# AlpLogo.net
KiCad netlist of a schematic drawn in Altium Designer
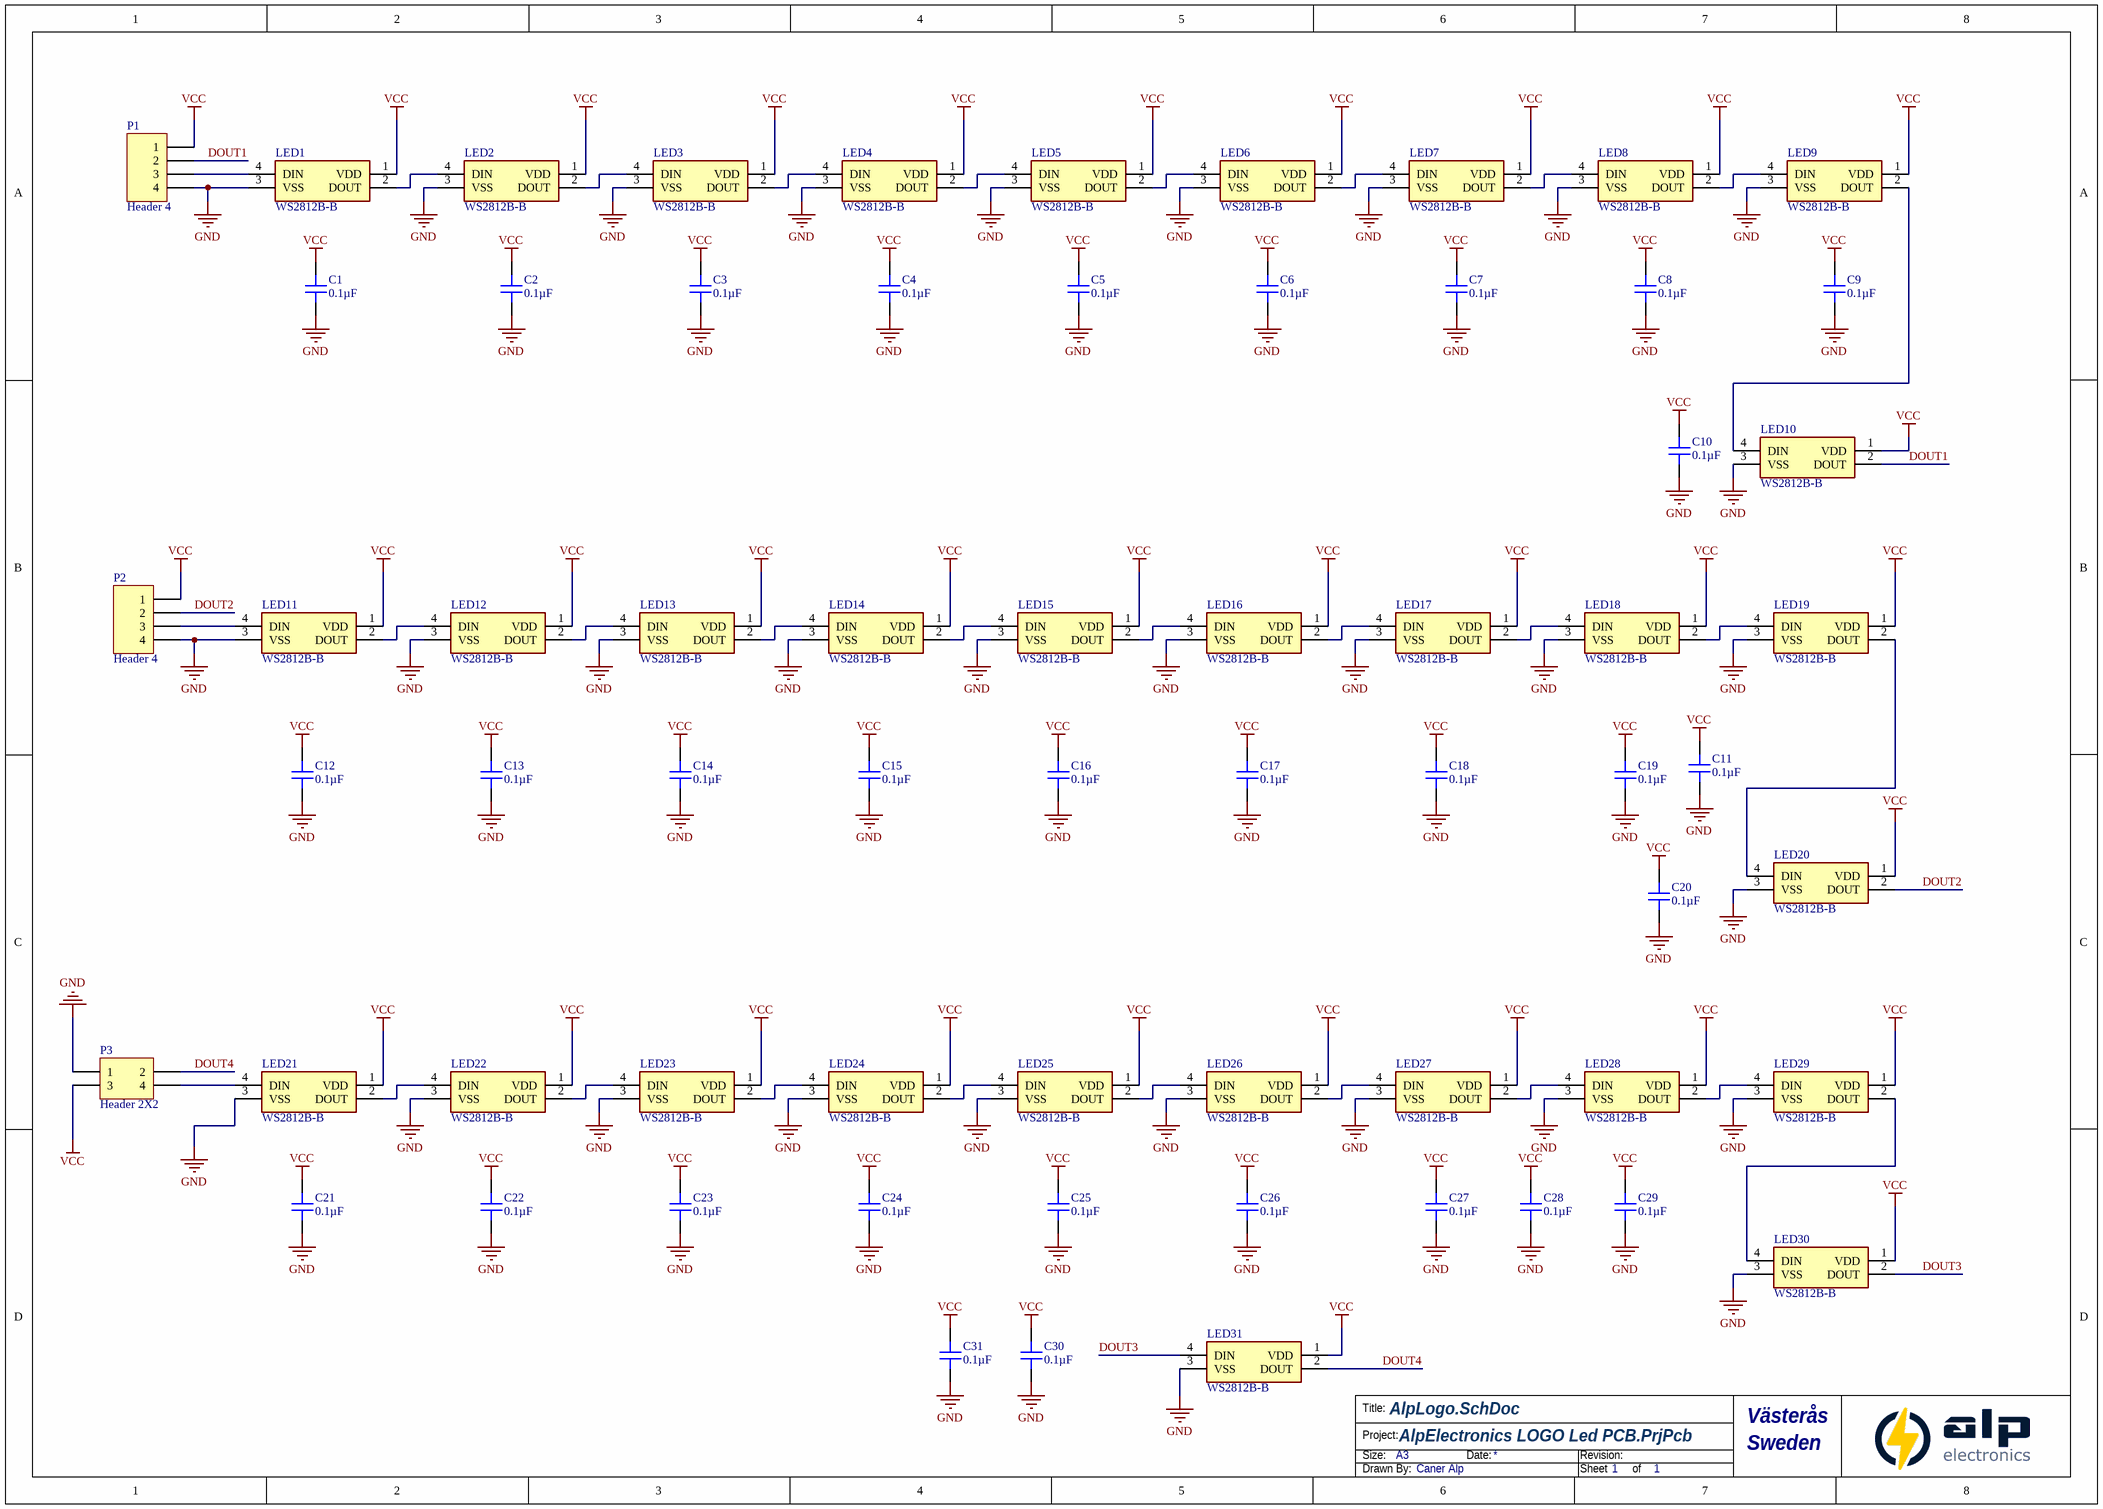
[diagram p0: AlpLogo.SchDoc]

(export (version "E")
  (design (tool "Eeschema 10.0.6"))
  (components
    (comp (ref "C1")
      (value "0.1µF")
      (footprint "CAP 0805_2012")
      (description "CAP CER 0.1UF 50V X7R 0805")
      (fields (field (name "PART NUMBER") "CC0805MRX7R9BB104") (field (name "MANUFACTURER") "Yageo"))
      (libsource (lib "Celestial Altium Library - altium_library") (part "Capacitor"))
    )
    (comp (ref "C2")
      (value "0.1µF")
      (footprint "CAP 0805_2012")
      (description "CAP CER 0.1UF 50V X7R 0805")
      (fields (field (name "PART NUMBER") "CC0805MRX7R9BB104") (field (name "MANUFACTURER") "Yageo"))
      (libsource (lib "Celestial Altium Library - altium_library") (part "Capacitor"))
    )
    (comp (ref "C3")
      (value "0.1µF")
      (footprint "CAP 0805_2012")
      (description "CAP CER 0.1UF 50V X7R 0805")
      (fields (field (name "PART NUMBER") "CC0805MRX7R9BB104") (field (name "MANUFACTURER") "Yageo"))
      (libsource (lib "Celestial Altium Library - altium_library") (part "Capacitor"))
    )
    (comp (ref "C4")
      (value "0.1µF")
      (footprint "CAP 0805_2012")
      (description "CAP CER 0.1UF 50V X7R 0805")
      (fields (field (name "PART NUMBER") "CC0805MRX7R9BB104") (field (name "MANUFACTURER") "Yageo"))
      (libsource (lib "Celestial Altium Library - altium_library") (part "Capacitor"))
    )
    (comp (ref "C5")
      (value "0.1µF")
      (footprint "CAP 0805_2012")
      (description "CAP CER 0.1UF 50V X7R 0805")
      (fields (field (name "PART NUMBER") "CC0805MRX7R9BB104") (field (name "MANUFACTURER") "Yageo"))
      (libsource (lib "Celestial Altium Library - altium_library") (part "Capacitor"))
    )
    (comp (ref "C6")
      (value "0.1µF")
      (footprint "CAP 0805_2012")
      (description "CAP CER 0.1UF 50V X7R 0805")
      (fields (field (name "PART NUMBER") "CC0805MRX7R9BB104") (field (name "MANUFACTURER") "Yageo"))
      (libsource (lib "Celestial Altium Library - altium_library") (part "Capacitor"))
    )
    (comp (ref "C7")
      (value "0.1µF")
      (footprint "CAP 0805_2012")
      (description "CAP CER 0.1UF 50V X7R 0805")
      (fields (field (name "PART NUMBER") "CC0805MRX7R9BB104") (field (name "MANUFACTURER") "Yageo"))
      (libsource (lib "Celestial Altium Library - altium_library") (part "Capacitor"))
    )
    (comp (ref "C8")
      (value "0.1µF")
      (footprint "CAP 0805_2012")
      (description "CAP CER 0.1UF 50V X7R 0805")
      (fields (field (name "PART NUMBER") "CC0805MRX7R9BB104") (field (name "MANUFACTURER") "Yageo"))
      (libsource (lib "Celestial Altium Library - altium_library") (part "Capacitor"))
    )
    (comp (ref "C9")
      (value "0.1µF")
      (footprint "CAP 0805_2012")
      (description "CAP CER 0.1UF 50V X7R 0805")
      (fields (field (name "PART NUMBER") "CC0805MRX7R9BB104") (field (name "MANUFACTURER") "Yageo"))
      (libsource (lib "Celestial Altium Library - altium_library") (part "Capacitor"))
    )
    (comp (ref "C10")
      (value "0.1µF")
      (footprint "CAP 0805_2012")
      (description "CAP CER 0.1UF 50V X7R 0805")
      (fields (field (name "PART NUMBER") "CC0805MRX7R9BB104") (field (name "MANUFACTURER") "Yageo"))
      (libsource (lib "Celestial Altium Library - altium_library") (part "Capacitor"))
    )
    (comp (ref "C11")
      (value "0.1µF")
      (footprint "CAP 0805_2012")
      (description "CAP CER 0.1UF 50V X7R 0805")
      (fields (field (name "PART NUMBER") "CC0805MRX7R9BB104") (field (name "MANUFACTURER") "Yageo"))
      (libsource (lib "Celestial Altium Library - altium_library") (part "Capacitor"))
    )
    (comp (ref "C12")
      (value "0.1µF")
      (footprint "CAP 0805_2012")
      (description "CAP CER 0.1UF 50V X7R 0805")
      (fields (field (name "PART NUMBER") "CC0805MRX7R9BB104") (field (name "MANUFACTURER") "Yageo"))
      (libsource (lib "Celestial Altium Library - altium_library") (part "Capacitor"))
    )
    (comp (ref "C13")
      (value "0.1µF")
      (footprint "CAP 0805_2012")
      (description "CAP CER 0.1UF 50V X7R 0805")
      (fields (field (name "PART NUMBER") "CC0805MRX7R9BB104") (field (name "MANUFACTURER") "Yageo"))
      (libsource (lib "Celestial Altium Library - altium_library") (part "Capacitor"))
    )
    (comp (ref "C14")
      (value "0.1µF")
      (footprint "CAP 0805_2012")
      (description "CAP CER 0.1UF 50V X7R 0805")
      (fields (field (name "PART NUMBER") "CC0805MRX7R9BB104") (field (name "MANUFACTURER") "Yageo"))
      (libsource (lib "Celestial Altium Library - altium_library") (part "Capacitor"))
    )
    (comp (ref "C15")
      (value "0.1µF")
      (footprint "CAP 0805_2012")
      (description "CAP CER 0.1UF 50V X7R 0805")
      (fields (field (name "PART NUMBER") "CC0805MRX7R9BB104") (field (name "MANUFACTURER") "Yageo"))
      (libsource (lib "Celestial Altium Library - altium_library") (part "Capacitor"))
    )
    (comp (ref "C16")
      (value "0.1µF")
      (footprint "CAP 0805_2012")
      (description "CAP CER 0.1UF 50V X7R 0805")
      (fields (field (name "PART NUMBER") "CC0805MRX7R9BB104") (field (name "MANUFACTURER") "Yageo"))
      (libsource (lib "Celestial Altium Library - altium_library") (part "Capacitor"))
    )
    (comp (ref "C17")
      (value "0.1µF")
      (footprint "CAP 0805_2012")
      (description "CAP CER 0.1UF 50V X7R 0805")
      (fields (field (name "PART NUMBER") "CC0805MRX7R9BB104") (field (name "MANUFACTURER") "Yageo"))
      (libsource (lib "Celestial Altium Library - altium_library") (part "Capacitor"))
    )
    (comp (ref "C18")
      (value "0.1µF")
      (footprint "CAP 0805_2012")
      (description "CAP CER 0.1UF 50V X7R 0805")
      (fields (field (name "PART NUMBER") "CC0805MRX7R9BB104") (field (name "MANUFACTURER") "Yageo"))
      (libsource (lib "Celestial Altium Library - altium_library") (part "Capacitor"))
    )
    (comp (ref "C19")
      (value "0.1µF")
      (footprint "CAP 0805_2012")
      (description "CAP CER 0.1UF 50V X7R 0805")
      (fields (field (name "PART NUMBER") "CC0805MRX7R9BB104") (field (name "MANUFACTURER") "Yageo"))
      (libsource (lib "Celestial Altium Library - altium_library") (part "Capacitor"))
    )
    (comp (ref "C20")
      (value "0.1µF")
      (footprint "CAP 0805_2012")
      (description "CAP CER 0.1UF 50V X7R 0805")
      (fields (field (name "PART NUMBER") "CC0805MRX7R9BB104") (field (name "MANUFACTURER") "Yageo"))
      (libsource (lib "Celestial Altium Library - altium_library") (part "Capacitor"))
    )
    (comp (ref "C21")
      (value "0.1µF")
      (footprint "CAP 0805_2012")
      (description "CAP CER 0.1UF 50V X7R 0805")
      (fields (field (name "PART NUMBER") "CC0805MRX7R9BB104") (field (name "MANUFACTURER") "Yageo"))
      (libsource (lib "Celestial Altium Library - altium_library") (part "Capacitor"))
    )
    (comp (ref "C22")
      (value "0.1µF")
      (footprint "CAP 0805_2012")
      (description "CAP CER 0.1UF 50V X7R 0805")
      (fields (field (name "PART NUMBER") "CC0805MRX7R9BB104") (field (name "MANUFACTURER") "Yageo"))
      (libsource (lib "Celestial Altium Library - altium_library") (part "Capacitor"))
    )
    (comp (ref "C23")
      (value "0.1µF")
      (footprint "CAP 0805_2012")
      (description "CAP CER 0.1UF 50V X7R 0805")
      (fields (field (name "PART NUMBER") "CC0805MRX7R9BB104") (field (name "MANUFACTURER") "Yageo"))
      (libsource (lib "Celestial Altium Library - altium_library") (part "Capacitor"))
    )
    (comp (ref "C24")
      (value "0.1µF")
      (footprint "CAP 0805_2012")
      (description "CAP CER 0.1UF 50V X7R 0805")
      (fields (field (name "PART NUMBER") "CC0805MRX7R9BB104") (field (name "MANUFACTURER") "Yageo"))
      (libsource (lib "Celestial Altium Library - altium_library") (part "Capacitor"))
    )
    (comp (ref "C25")
      (value "0.1µF")
      (footprint "CAP 0805_2012")
      (description "CAP CER 0.1UF 50V X7R 0805")
      (fields (field (name "PART NUMBER") "CC0805MRX7R9BB104") (field (name "MANUFACTURER") "Yageo"))
      (libsource (lib "Celestial Altium Library - altium_library") (part "Capacitor"))
    )
    (comp (ref "C26")
      (value "0.1µF")
      (footprint "CAP 0805_2012")
      (description "CAP CER 0.1UF 50V X7R 0805")
      (fields (field (name "PART NUMBER") "CC0805MRX7R9BB104") (field (name "MANUFACTURER") "Yageo"))
      (libsource (lib "Celestial Altium Library - altium_library") (part "Capacitor"))
    )
    (comp (ref "C27")
      (value "0.1µF")
      (footprint "CAP 0805_2012")
      (description "CAP CER 0.1UF 50V X7R 0805")
      (fields (field (name "PART NUMBER") "CC0805MRX7R9BB104") (field (name "MANUFACTURER") "Yageo"))
      (libsource (lib "Celestial Altium Library - altium_library") (part "Capacitor"))
    )
    (comp (ref "C28")
      (value "0.1µF")
      (footprint "CAP 0805_2012")
      (description "CAP CER 0.1UF 50V X7R 0805")
      (fields (field (name "PART NUMBER") "CC0805MRX7R9BB104") (field (name "MANUFACTURER") "Yageo"))
      (libsource (lib "Celestial Altium Library - altium_library") (part "Capacitor"))
    )
    (comp (ref "C29")
      (value "0.1µF")
      (footprint "CAP 0805_2012")
      (description "CAP CER 0.1UF 50V X7R 0805")
      (fields (field (name "PART NUMBER") "CC0805MRX7R9BB104") (field (name "MANUFACTURER") "Yageo"))
      (libsource (lib "Celestial Altium Library - altium_library") (part "Capacitor"))
    )
    (comp (ref "C30")
      (value "0.1µF")
      (footprint "CAP 0805_2012")
      (description "CAP CER 0.1UF 50V X7R 0805")
      (fields (field (name "PART NUMBER") "CC0805MRX7R9BB104") (field (name "MANUFACTURER") "Yageo"))
      (libsource (lib "Celestial Altium Library - altium_library") (part "Capacitor"))
    )
    (comp (ref "C31")
      (value "0.1µF")
      (footprint "CAP 0805_2012")
      (description "CAP CER 0.1UF 50V X7R 0805")
      (fields (field (name "PART NUMBER") "CC0805MRX7R9BB104") (field (name "MANUFACTURER") "Yageo"))
      (libsource (lib "Celestial Altium Library - altium_library") (part "Capacitor"))
    )
    (comp (ref "LED1")
      (value "WS2812B-B")
      (footprint "AlpLogo:WS2812BB")
      (description "LED")
      (libsource (lib "AlpLogo") (part "WS2812B-B"))
    )
    (comp (ref "LED2")
      (value "WS2812B-B")
      (footprint "AlpLogo:WS2812BB")
      (description "LED")
      (libsource (lib "AlpLogo") (part "WS2812B-B"))
    )
    (comp (ref "LED3")
      (value "WS2812B-B")
      (footprint "AlpLogo:WS2812BB")
      (description "LED")
      (libsource (lib "AlpLogo") (part "WS2812B-B"))
    )
    (comp (ref "LED4")
      (value "WS2812B-B")
      (footprint "AlpLogo:WS2812BB")
      (description "LED")
      (libsource (lib "AlpLogo") (part "WS2812B-B"))
    )
    (comp (ref "LED5")
      (value "WS2812B-B")
      (footprint "AlpLogo:WS2812BB")
      (description "LED")
      (libsource (lib "AlpLogo") (part "WS2812B-B"))
    )
    (comp (ref "LED6")
      (value "WS2812B-B")
      (footprint "AlpLogo:WS2812BB")
      (description "LED")
      (libsource (lib "AlpLogo") (part "WS2812B-B"))
    )
    (comp (ref "LED7")
      (value "WS2812B-B")
      (footprint "AlpLogo:WS2812BB")
      (description "LED")
      (libsource (lib "AlpLogo") (part "WS2812B-B"))
    )
    (comp (ref "LED8")
      (value "WS2812B-B")
      (footprint "AlpLogo:WS2812BB")
      (description "LED")
      (libsource (lib "AlpLogo") (part "WS2812B-B"))
    )
    (comp (ref "LED9")
      (value "WS2812B-B")
      (footprint "AlpLogo:WS2812BB")
      (description "LED")
      (libsource (lib "AlpLogo") (part "WS2812B-B"))
    )
    (comp (ref "LED10")
      (value "WS2812B-B")
      (footprint "AlpLogo:WS2812BB")
      (description "LED")
      (libsource (lib "AlpLogo") (part "WS2812B-B"))
    )
    (comp (ref "LED11")
      (value "WS2812B-B")
      (footprint "AlpLogo:WS2812BB")
      (description "LED")
      (libsource (lib "AlpLogo") (part "WS2812B-B"))
    )
    (comp (ref "LED12")
      (value "WS2812B-B")
      (footprint "AlpLogo:WS2812BB")
      (description "LED")
      (libsource (lib "AlpLogo") (part "WS2812B-B"))
    )
    (comp (ref "LED13")
      (value "WS2812B-B")
      (footprint "AlpLogo:WS2812BB")
      (description "LED")
      (libsource (lib "AlpLogo") (part "WS2812B-B"))
    )
    (comp (ref "LED14")
      (value "WS2812B-B")
      (footprint "AlpLogo:WS2812BB")
      (description "LED")
      (libsource (lib "AlpLogo") (part "WS2812B-B"))
    )
    (comp (ref "LED15")
      (value "WS2812B-B")
      (footprint "AlpLogo:WS2812BB")
      (description "LED")
      (libsource (lib "AlpLogo") (part "WS2812B-B"))
    )
    (comp (ref "LED16")
      (value "WS2812B-B")
      (footprint "AlpLogo:WS2812BB")
      (description "LED")
      (libsource (lib "AlpLogo") (part "WS2812B-B"))
    )
    (comp (ref "LED17")
      (value "WS2812B-B")
      (footprint "AlpLogo:WS2812BB")
      (description "LED")
      (libsource (lib "AlpLogo") (part "WS2812B-B"))
    )
    (comp (ref "LED18")
      (value "WS2812B-B")
      (footprint "AlpLogo:WS2812BB")
      (description "LED")
      (libsource (lib "AlpLogo") (part "WS2812B-B"))
    )
    (comp (ref "LED19")
      (value "WS2812B-B")
      (footprint "AlpLogo:WS2812BB")
      (description "LED")
      (libsource (lib "AlpLogo") (part "WS2812B-B"))
    )
    (comp (ref "LED20")
      (value "WS2812B-B")
      (footprint "AlpLogo:WS2812BB")
      (description "LED")
      (libsource (lib "AlpLogo") (part "WS2812B-B"))
    )
    (comp (ref "LED21")
      (value "WS2812B-B")
      (footprint "AlpLogo:WS2812BB")
      (description "LED")
      (libsource (lib "AlpLogo") (part "WS2812B-B"))
    )
    (comp (ref "LED22")
      (value "WS2812B-B")
      (footprint "AlpLogo:WS2812BB")
      (description "LED")
      (libsource (lib "AlpLogo") (part "WS2812B-B"))
    )
    (comp (ref "LED23")
      (value "WS2812B-B")
      (footprint "AlpLogo:WS2812BB")
      (description "LED")
      (libsource (lib "AlpLogo") (part "WS2812B-B"))
    )
    (comp (ref "LED24")
      (value "WS2812B-B")
      (footprint "AlpLogo:WS2812BB")
      (description "LED")
      (libsource (lib "AlpLogo") (part "WS2812B-B"))
    )
    (comp (ref "LED25")
      (value "WS2812B-B")
      (footprint "AlpLogo:WS2812BB")
      (description "LED")
      (libsource (lib "AlpLogo") (part "WS2812B-B"))
    )
    (comp (ref "LED26")
      (value "WS2812B-B")
      (footprint "AlpLogo:WS2812BB")
      (description "LED")
      (libsource (lib "AlpLogo") (part "WS2812B-B"))
    )
    (comp (ref "LED27")
      (value "WS2812B-B")
      (footprint "AlpLogo:WS2812BB")
      (description "LED")
      (libsource (lib "AlpLogo") (part "WS2812B-B"))
    )
    (comp (ref "LED28")
      (value "WS2812B-B")
      (footprint "AlpLogo:WS2812BB")
      (description "LED")
      (libsource (lib "AlpLogo") (part "WS2812B-B"))
    )
    (comp (ref "LED29")
      (value "WS2812B-B")
      (footprint "AlpLogo:WS2812BB")
      (description "LED")
      (libsource (lib "AlpLogo") (part "WS2812B-B"))
    )
    (comp (ref "LED30")
      (value "WS2812B-B")
      (footprint "AlpLogo:WS2812BB")
      (description "LED")
      (libsource (lib "AlpLogo") (part "WS2812B-B"))
    )
    (comp (ref "LED31")
      (value "WS2812B-B")
      (footprint "AlpLogo:WS2812BB")
      (description "LED")
      (libsource (lib "AlpLogo") (part "WS2812B-B"))
    )
    (comp (ref "P1")
      (value "Header 4")
      (footprint "HDR1X4")
      (description "Header, 4-Pin")
      (fields (field (name "PUBLISHER") "Altium Limited"))
      (libsource (lib "Miscellaneous Connectors") (part "Header 4"))
    )
    (comp (ref "P2")
      (value "Header 4")
      (footprint "HDR1X4")
      (description "Header, 4-Pin")
      (fields (field (name "PUBLISHER") "Altium Limited"))
      (libsource (lib "Miscellaneous Connectors") (part "Header 4"))
    )
    (comp (ref "P3")
      (value "Header 2X2")
      (footprint "HDR2X2")
      (description "Header, 2-Pin, Dual row")
      (fields (field (name "PUBLISHER") "Altium Limited"))
      (libsource (lib "Miscellaneous Connectors") (part "Header 2X2"))
    )
  )
  (nets
    (net (code "1") (name "/DOUT1") (class "Default")
      (node (ref "LED10") (pin "2") (pinfunction "DOUT_2") (pintype "passive"))
      (node (ref "P1") (pin "2") (pinfunction "2_2") (pintype "passive"))
    )
    (net (code "2") (name "/DOUT2") (class "Default")
      (node (ref "LED20") (pin "2") (pinfunction "DOUT_2") (pintype "passive"))
      (node (ref "P2") (pin "2") (pinfunction "2_2") (pintype "passive"))
    )
    (net (code "3") (name "/DOUT3") (class "Default")
      (node (ref "LED30") (pin "2") (pinfunction "DOUT_2") (pintype "passive"))
      (node (ref "LED31") (pin "4") (pinfunction "DIN_4") (pintype "passive"))
    )
    (net (code "4") (name "/DOUT4") (class "Default")
      (node (ref "LED31") (pin "2") (pinfunction "DOUT_2") (pintype "passive"))
      (node (ref "P3") (pin "2") (pinfunction "2_2") (pintype "passive"))
    )
    (net (code "5") (name "GND") (class "Default")
      (node (ref "C1") (pin "1") (pinfunction "1_1") (pintype "passive"))
      (node (ref "C10") (pin "1") (pinfunction "1_1") (pintype "passive"))
      (node (ref "C11") (pin "1") (pinfunction "1_1") (pintype "passive"))
      (node (ref "C12") (pin "1") (pinfunction "1_1") (pintype "passive"))
      (node (ref "C13") (pin "1") (pinfunction "1_1") (pintype "passive"))
      (node (ref "C14") (pin "1") (pinfunction "1_1") (pintype "passive"))
      (node (ref "C15") (pin "1") (pinfunction "1_1") (pintype "passive"))
      (node (ref "C16") (pin "1") (pinfunction "1_1") (pintype "passive"))
      (node (ref "C17") (pin "1") (pinfunction "1_1") (pintype "passive"))
      (node (ref "C18") (pin "1") (pinfunction "1_1") (pintype "passive"))
      (node (ref "C19") (pin "1") (pinfunction "1_1") (pintype "passive"))
      (node (ref "C2") (pin "1") (pinfunction "1_1") (pintype "passive"))
      (node (ref "C20") (pin "1") (pinfunction "1_1") (pintype "passive"))
      (node (ref "C21") (pin "1") (pinfunction "1_1") (pintype "passive"))
      (node (ref "C22") (pin "1") (pinfunction "1_1") (pintype "passive"))
      (node (ref "C23") (pin "1") (pinfunction "1_1") (pintype "passive"))
      (node (ref "C24") (pin "1") (pinfunction "1_1") (pintype "passive"))
      (node (ref "C25") (pin "1") (pinfunction "1_1") (pintype "passive"))
      (node (ref "C26") (pin "1") (pinfunction "1_1") (pintype "passive"))
      (node (ref "C27") (pin "1") (pinfunction "1_1") (pintype "passive"))
      (node (ref "C28") (pin "1") (pinfunction "1_1") (pintype "passive"))
      (node (ref "C29") (pin "1") (pinfunction "1_1") (pintype "passive"))
      (node (ref "C3") (pin "1") (pinfunction "1_1") (pintype "passive"))
      (node (ref "C30") (pin "1") (pinfunction "1_1") (pintype "passive"))
      (node (ref "C31") (pin "1") (pinfunction "1_1") (pintype "passive"))
      (node (ref "C4") (pin "1") (pinfunction "1_1") (pintype "passive"))
      (node (ref "C5") (pin "1") (pinfunction "1_1") (pintype "passive"))
      (node (ref "C6") (pin "1") (pinfunction "1_1") (pintype "passive"))
      (node (ref "C7") (pin "1") (pinfunction "1_1") (pintype "passive"))
      (node (ref "C8") (pin "1") (pinfunction "1_1") (pintype "passive"))
      (node (ref "C9") (pin "1") (pinfunction "1_1") (pintype "passive"))
      (node (ref "LED1") (pin "3") (pinfunction "VSS_3") (pintype "passive"))
      (node (ref "LED10") (pin "3") (pinfunction "VSS_3") (pintype "passive"))
      (node (ref "LED11") (pin "3") (pinfunction "VSS_3") (pintype "passive"))
      (node (ref "LED12") (pin "3") (pinfunction "VSS_3") (pintype "passive"))
      (node (ref "LED13") (pin "3") (pinfunction "VSS_3") (pintype "passive"))
      (node (ref "LED14") (pin "3") (pinfunction "VSS_3") (pintype "passive"))
      (node (ref "LED15") (pin "3") (pinfunction "VSS_3") (pintype "passive"))
      (node (ref "LED16") (pin "3") (pinfunction "VSS_3") (pintype "passive"))
      (node (ref "LED17") (pin "3") (pinfunction "VSS_3") (pintype "passive"))
      (node (ref "LED18") (pin "3") (pinfunction "VSS_3") (pintype "passive"))
      (node (ref "LED19") (pin "3") (pinfunction "VSS_3") (pintype "passive"))
      (node (ref "LED2") (pin "3") (pinfunction "VSS_3") (pintype "passive"))
      (node (ref "LED20") (pin "3") (pinfunction "VSS_3") (pintype "passive"))
      (node (ref "LED21") (pin "3") (pinfunction "VSS_3") (pintype "passive"))
      (node (ref "LED22") (pin "3") (pinfunction "VSS_3") (pintype "passive"))
      (node (ref "LED23") (pin "3") (pinfunction "VSS_3") (pintype "passive"))
      (node (ref "LED24") (pin "3") (pinfunction "VSS_3") (pintype "passive"))
      (node (ref "LED25") (pin "3") (pinfunction "VSS_3") (pintype "passive"))
      (node (ref "LED26") (pin "3") (pinfunction "VSS_3") (pintype "passive"))
      (node (ref "LED27") (pin "3") (pinfunction "VSS_3") (pintype "passive"))
      (node (ref "LED28") (pin "3") (pinfunction "VSS_3") (pintype "passive"))
      (node (ref "LED29") (pin "3") (pinfunction "VSS_3") (pintype "passive"))
      (node (ref "LED3") (pin "3") (pinfunction "VSS_3") (pintype "passive"))
      (node (ref "LED30") (pin "3") (pinfunction "VSS_3") (pintype "passive"))
      (node (ref "LED31") (pin "3") (pinfunction "VSS_3") (pintype "passive"))
      (node (ref "LED4") (pin "3") (pinfunction "VSS_3") (pintype "passive"))
      (node (ref "LED5") (pin "3") (pinfunction "VSS_3") (pintype "passive"))
      (node (ref "LED6") (pin "3") (pinfunction "VSS_3") (pintype "passive"))
      (node (ref "LED7") (pin "3") (pinfunction "VSS_3") (pintype "passive"))
      (node (ref "LED8") (pin "3") (pinfunction "VSS_3") (pintype "passive"))
      (node (ref "LED9") (pin "3") (pinfunction "VSS_3") (pintype "passive"))
      (node (ref "P1") (pin "4") (pinfunction "4_4") (pintype "passive"))
      (node (ref "P2") (pin "4") (pinfunction "4_4") (pintype "passive"))
      (node (ref "P3") (pin "1") (pinfunction "1_1") (pintype "passive"))
    )
    (net (code "6") (name "Net-(LED1-DIN)") (class "Default")
      (node (ref "LED1") (pin "4") (pinfunction "DIN_4") (pintype "passive"))
      (node (ref "P1") (pin "3") (pinfunction "3_3") (pintype "passive"))
    )
    (net (code "7") (name "Net-(LED1-DOUT)") (class "Default")
      (node (ref "LED1") (pin "2") (pinfunction "DOUT_2") (pintype "passive"))
      (node (ref "LED2") (pin "4") (pinfunction "DIN_4") (pintype "passive"))
    )
    (net (code "8") (name "Net-(LED2-DOUT)") (class "Default")
      (node (ref "LED2") (pin "2") (pinfunction "DOUT_2") (pintype "passive"))
      (node (ref "LED3") (pin "4") (pinfunction "DIN_4") (pintype "passive"))
    )
    (net (code "9") (name "Net-(LED3-DOUT)") (class "Default")
      (node (ref "LED3") (pin "2") (pinfunction "DOUT_2") (pintype "passive"))
      (node (ref "LED4") (pin "4") (pinfunction "DIN_4") (pintype "passive"))
    )
    (net (code "10") (name "Net-(LED4-DOUT)") (class "Default")
      (node (ref "LED4") (pin "2") (pinfunction "DOUT_2") (pintype "passive"))
      (node (ref "LED5") (pin "4") (pinfunction "DIN_4") (pintype "passive"))
    )
    (net (code "11") (name "Net-(LED5-DOUT)") (class "Default")
      (node (ref "LED5") (pin "2") (pinfunction "DOUT_2") (pintype "passive"))
      (node (ref "LED6") (pin "4") (pinfunction "DIN_4") (pintype "passive"))
    )
    (net (code "12") (name "Net-(LED6-DOUT)") (class "Default")
      (node (ref "LED6") (pin "2") (pinfunction "DOUT_2") (pintype "passive"))
      (node (ref "LED7") (pin "4") (pinfunction "DIN_4") (pintype "passive"))
    )
    (net (code "13") (name "Net-(LED7-DOUT)") (class "Default")
      (node (ref "LED7") (pin "2") (pinfunction "DOUT_2") (pintype "passive"))
      (node (ref "LED8") (pin "4") (pinfunction "DIN_4") (pintype "passive"))
    )
    (net (code "14") (name "Net-(LED8-DOUT)") (class "Default")
      (node (ref "LED8") (pin "2") (pinfunction "DOUT_2") (pintype "passive"))
      (node (ref "LED9") (pin "4") (pinfunction "DIN_4") (pintype "passive"))
    )
    (net (code "15") (name "Net-(LED10-DIN)") (class "Default")
      (node (ref "LED10") (pin "4") (pinfunction "DIN_4") (pintype "passive"))
      (node (ref "LED9") (pin "2") (pinfunction "DOUT_2") (pintype "passive"))
    )
    (net (code "16") (name "Net-(LED11-DIN)") (class "Default")
      (node (ref "LED11") (pin "4") (pinfunction "DIN_4") (pintype "passive"))
      (node (ref "P2") (pin "3") (pinfunction "3_3") (pintype "passive"))
    )
    (net (code "17") (name "Net-(LED11-DOUT)") (class "Default")
      (node (ref "LED11") (pin "2") (pinfunction "DOUT_2") (pintype "passive"))
      (node (ref "LED12") (pin "4") (pinfunction "DIN_4") (pintype "passive"))
    )
    (net (code "18") (name "Net-(LED12-DOUT)") (class "Default")
      (node (ref "LED12") (pin "2") (pinfunction "DOUT_2") (pintype "passive"))
      (node (ref "LED13") (pin "4") (pinfunction "DIN_4") (pintype "passive"))
    )
    (net (code "19") (name "Net-(LED13-DOUT)") (class "Default")
      (node (ref "LED13") (pin "2") (pinfunction "DOUT_2") (pintype "passive"))
      (node (ref "LED14") (pin "4") (pinfunction "DIN_4") (pintype "passive"))
    )
    (net (code "20") (name "Net-(LED14-DOUT)") (class "Default")
      (node (ref "LED14") (pin "2") (pinfunction "DOUT_2") (pintype "passive"))
      (node (ref "LED15") (pin "4") (pinfunction "DIN_4") (pintype "passive"))
    )
    (net (code "21") (name "Net-(LED15-DOUT)") (class "Default")
      (node (ref "LED15") (pin "2") (pinfunction "DOUT_2") (pintype "passive"))
      (node (ref "LED16") (pin "4") (pinfunction "DIN_4") (pintype "passive"))
    )
    (net (code "22") (name "Net-(LED16-DOUT)") (class "Default")
      (node (ref "LED16") (pin "2") (pinfunction "DOUT_2") (pintype "passive"))
      (node (ref "LED17") (pin "4") (pinfunction "DIN_4") (pintype "passive"))
    )
    (net (code "23") (name "Net-(LED17-DOUT)") (class "Default")
      (node (ref "LED17") (pin "2") (pinfunction "DOUT_2") (pintype "passive"))
      (node (ref "LED18") (pin "4") (pinfunction "DIN_4") (pintype "passive"))
    )
    (net (code "24") (name "Net-(LED18-DOUT)") (class "Default")
      (node (ref "LED18") (pin "2") (pinfunction "DOUT_2") (pintype "passive"))
      (node (ref "LED19") (pin "4") (pinfunction "DIN_4") (pintype "passive"))
    )
    (net (code "25") (name "Net-(LED19-DOUT)") (class "Default")
      (node (ref "LED19") (pin "2") (pinfunction "DOUT_2") (pintype "passive"))
      (node (ref "LED20") (pin "4") (pinfunction "DIN_4") (pintype "passive"))
    )
    (net (code "26") (name "Net-(LED21-DIN)") (class "Default")
      (node (ref "LED21") (pin "4") (pinfunction "DIN_4") (pintype "passive"))
      (node (ref "P3") (pin "4") (pinfunction "4_4") (pintype "passive"))
    )
    (net (code "27") (name "Net-(LED21-DOUT)") (class "Default")
      (node (ref "LED21") (pin "2") (pinfunction "DOUT_2") (pintype "passive"))
      (node (ref "LED22") (pin "4") (pinfunction "DIN_4") (pintype "passive"))
    )
    (net (code "28") (name "Net-(LED22-DOUT)") (class "Default")
      (node (ref "LED22") (pin "2") (pinfunction "DOUT_2") (pintype "passive"))
      (node (ref "LED23") (pin "4") (pinfunction "DIN_4") (pintype "passive"))
    )
    (net (code "29") (name "Net-(LED23-DOUT)") (class "Default")
      (node (ref "LED23") (pin "2") (pinfunction "DOUT_2") (pintype "passive"))
      (node (ref "LED24") (pin "4") (pinfunction "DIN_4") (pintype "passive"))
    )
    (net (code "30") (name "Net-(LED24-DOUT)") (class "Default")
      (node (ref "LED24") (pin "2") (pinfunction "DOUT_2") (pintype "passive"))
      (node (ref "LED25") (pin "4") (pinfunction "DIN_4") (pintype "passive"))
    )
    (net (code "31") (name "Net-(LED25-DOUT)") (class "Default")
      (node (ref "LED25") (pin "2") (pinfunction "DOUT_2") (pintype "passive"))
      (node (ref "LED26") (pin "4") (pinfunction "DIN_4") (pintype "passive"))
    )
    (net (code "32") (name "Net-(LED26-DOUT)") (class "Default")
      (node (ref "LED26") (pin "2") (pinfunction "DOUT_2") (pintype "passive"))
      (node (ref "LED27") (pin "4") (pinfunction "DIN_4") (pintype "passive"))
    )
    (net (code "33") (name "Net-(LED27-DOUT)") (class "Default")
      (node (ref "LED27") (pin "2") (pinfunction "DOUT_2") (pintype "passive"))
      (node (ref "LED28") (pin "4") (pinfunction "DIN_4") (pintype "passive"))
    )
    (net (code "34") (name "Net-(LED28-DOUT)") (class "Default")
      (node (ref "LED28") (pin "2") (pinfunction "DOUT_2") (pintype "passive"))
      (node (ref "LED29") (pin "4") (pinfunction "DIN_4") (pintype "passive"))
    )
    (net (code "35") (name "Net-(LED29-DOUT)") (class "Default")
      (node (ref "LED29") (pin "2") (pinfunction "DOUT_2") (pintype "passive"))
      (node (ref "LED30") (pin "4") (pinfunction "DIN_4") (pintype "passive"))
    )
    (net (code "36") (name "VCC") (class "Default")
      (node (ref "C1") (pin "2") (pinfunction "2_2") (pintype "passive"))
      (node (ref "C10") (pin "2") (pinfunction "2_2") (pintype "passive"))
      (node (ref "C11") (pin "2") (pinfunction "2_2") (pintype "passive"))
      (node (ref "C12") (pin "2") (pinfunction "2_2") (pintype "passive"))
      (node (ref "C13") (pin "2") (pinfunction "2_2") (pintype "passive"))
      (node (ref "C14") (pin "2") (pinfunction "2_2") (pintype "passive"))
      (node (ref "C15") (pin "2") (pinfunction "2_2") (pintype "passive"))
      (node (ref "C16") (pin "2") (pinfunction "2_2") (pintype "passive"))
      (node (ref "C17") (pin "2") (pinfunction "2_2") (pintype "passive"))
      (node (ref "C18") (pin "2") (pinfunction "2_2") (pintype "passive"))
      (node (ref "C19") (pin "2") (pinfunction "2_2") (pintype "passive"))
      (node (ref "C2") (pin "2") (pinfunction "2_2") (pintype "passive"))
      (node (ref "C20") (pin "2") (pinfunction "2_2") (pintype "passive"))
      (node (ref "C21") (pin "2") (pinfunction "2_2") (pintype "passive"))
      (node (ref "C22") (pin "2") (pinfunction "2_2") (pintype "passive"))
      (node (ref "C23") (pin "2") (pinfunction "2_2") (pintype "passive"))
      (node (ref "C24") (pin "2") (pinfunction "2_2") (pintype "passive"))
      (node (ref "C25") (pin "2") (pinfunction "2_2") (pintype "passive"))
      (node (ref "C26") (pin "2") (pinfunction "2_2") (pintype "passive"))
      (node (ref "C27") (pin "2") (pinfunction "2_2") (pintype "passive"))
      (node (ref "C28") (pin "2") (pinfunction "2_2") (pintype "passive"))
      (node (ref "C29") (pin "2") (pinfunction "2_2") (pintype "passive"))
      (node (ref "C3") (pin "2") (pinfunction "2_2") (pintype "passive"))
      (node (ref "C30") (pin "2") (pinfunction "2_2") (pintype "passive"))
      (node (ref "C31") (pin "2") (pinfunction "2_2") (pintype "passive"))
      (node (ref "C4") (pin "2") (pinfunction "2_2") (pintype "passive"))
      (node (ref "C5") (pin "2") (pinfunction "2_2") (pintype "passive"))
      (node (ref "C6") (pin "2") (pinfunction "2_2") (pintype "passive"))
      (node (ref "C7") (pin "2") (pinfunction "2_2") (pintype "passive"))
      (node (ref "C8") (pin "2") (pinfunction "2_2") (pintype "passive"))
      (node (ref "C9") (pin "2") (pinfunction "2_2") (pintype "passive"))
      (node (ref "LED1") (pin "1") (pinfunction "VDD_1") (pintype "passive"))
      (node (ref "LED10") (pin "1") (pinfunction "VDD_1") (pintype "passive"))
      (node (ref "LED11") (pin "1") (pinfunction "VDD_1") (pintype "passive"))
      (node (ref "LED12") (pin "1") (pinfunction "VDD_1") (pintype "passive"))
      (node (ref "LED13") (pin "1") (pinfunction "VDD_1") (pintype "passive"))
      (node (ref "LED14") (pin "1") (pinfunction "VDD_1") (pintype "passive"))
      (node (ref "LED15") (pin "1") (pinfunction "VDD_1") (pintype "passive"))
      (node (ref "LED16") (pin "1") (pinfunction "VDD_1") (pintype "passive"))
      (node (ref "LED17") (pin "1") (pinfunction "VDD_1") (pintype "passive"))
      (node (ref "LED18") (pin "1") (pinfunction "VDD_1") (pintype "passive"))
      (node (ref "LED19") (pin "1") (pinfunction "VDD_1") (pintype "passive"))
      (node (ref "LED2") (pin "1") (pinfunction "VDD_1") (pintype "passive"))
      (node (ref "LED20") (pin "1") (pinfunction "VDD_1") (pintype "passive"))
      (node (ref "LED21") (pin "1") (pinfunction "VDD_1") (pintype "passive"))
      (node (ref "LED22") (pin "1") (pinfunction "VDD_1") (pintype "passive"))
      (node (ref "LED23") (pin "1") (pinfunction "VDD_1") (pintype "passive"))
      (node (ref "LED24") (pin "1") (pinfunction "VDD_1") (pintype "passive"))
      (node (ref "LED25") (pin "1") (pinfunction "VDD_1") (pintype "passive"))
      (node (ref "LED26") (pin "1") (pinfunction "VDD_1") (pintype "passive"))
      (node (ref "LED27") (pin "1") (pinfunction "VDD_1") (pintype "passive"))
      (node (ref "LED28") (pin "1") (pinfunction "VDD_1") (pintype "passive"))
      (node (ref "LED29") (pin "1") (pinfunction "VDD_1") (pintype "passive"))
      (node (ref "LED3") (pin "1") (pinfunction "VDD_1") (pintype "passive"))
      (node (ref "LED30") (pin "1") (pinfunction "VDD_1") (pintype "passive"))
      (node (ref "LED31") (pin "1") (pinfunction "VDD_1") (pintype "passive"))
      (node (ref "LED4") (pin "1") (pinfunction "VDD_1") (pintype "passive"))
      (node (ref "LED5") (pin "1") (pinfunction "VDD_1") (pintype "passive"))
      (node (ref "LED6") (pin "1") (pinfunction "VDD_1") (pintype "passive"))
      (node (ref "LED7") (pin "1") (pinfunction "VDD_1") (pintype "passive"))
      (node (ref "LED8") (pin "1") (pinfunction "VDD_1") (pintype "passive"))
      (node (ref "LED9") (pin "1") (pinfunction "VDD_1") (pintype "passive"))
      (node (ref "P1") (pin "1") (pinfunction "1_1") (pintype "passive"))
      (node (ref "P2") (pin "1") (pinfunction "1_1") (pintype "passive"))
      (node (ref "P3") (pin "3") (pinfunction "3_3") (pintype "passive"))
    )
  )
)
